# controller12.net
KiCad netlist of a schematic drawn in EAGLE
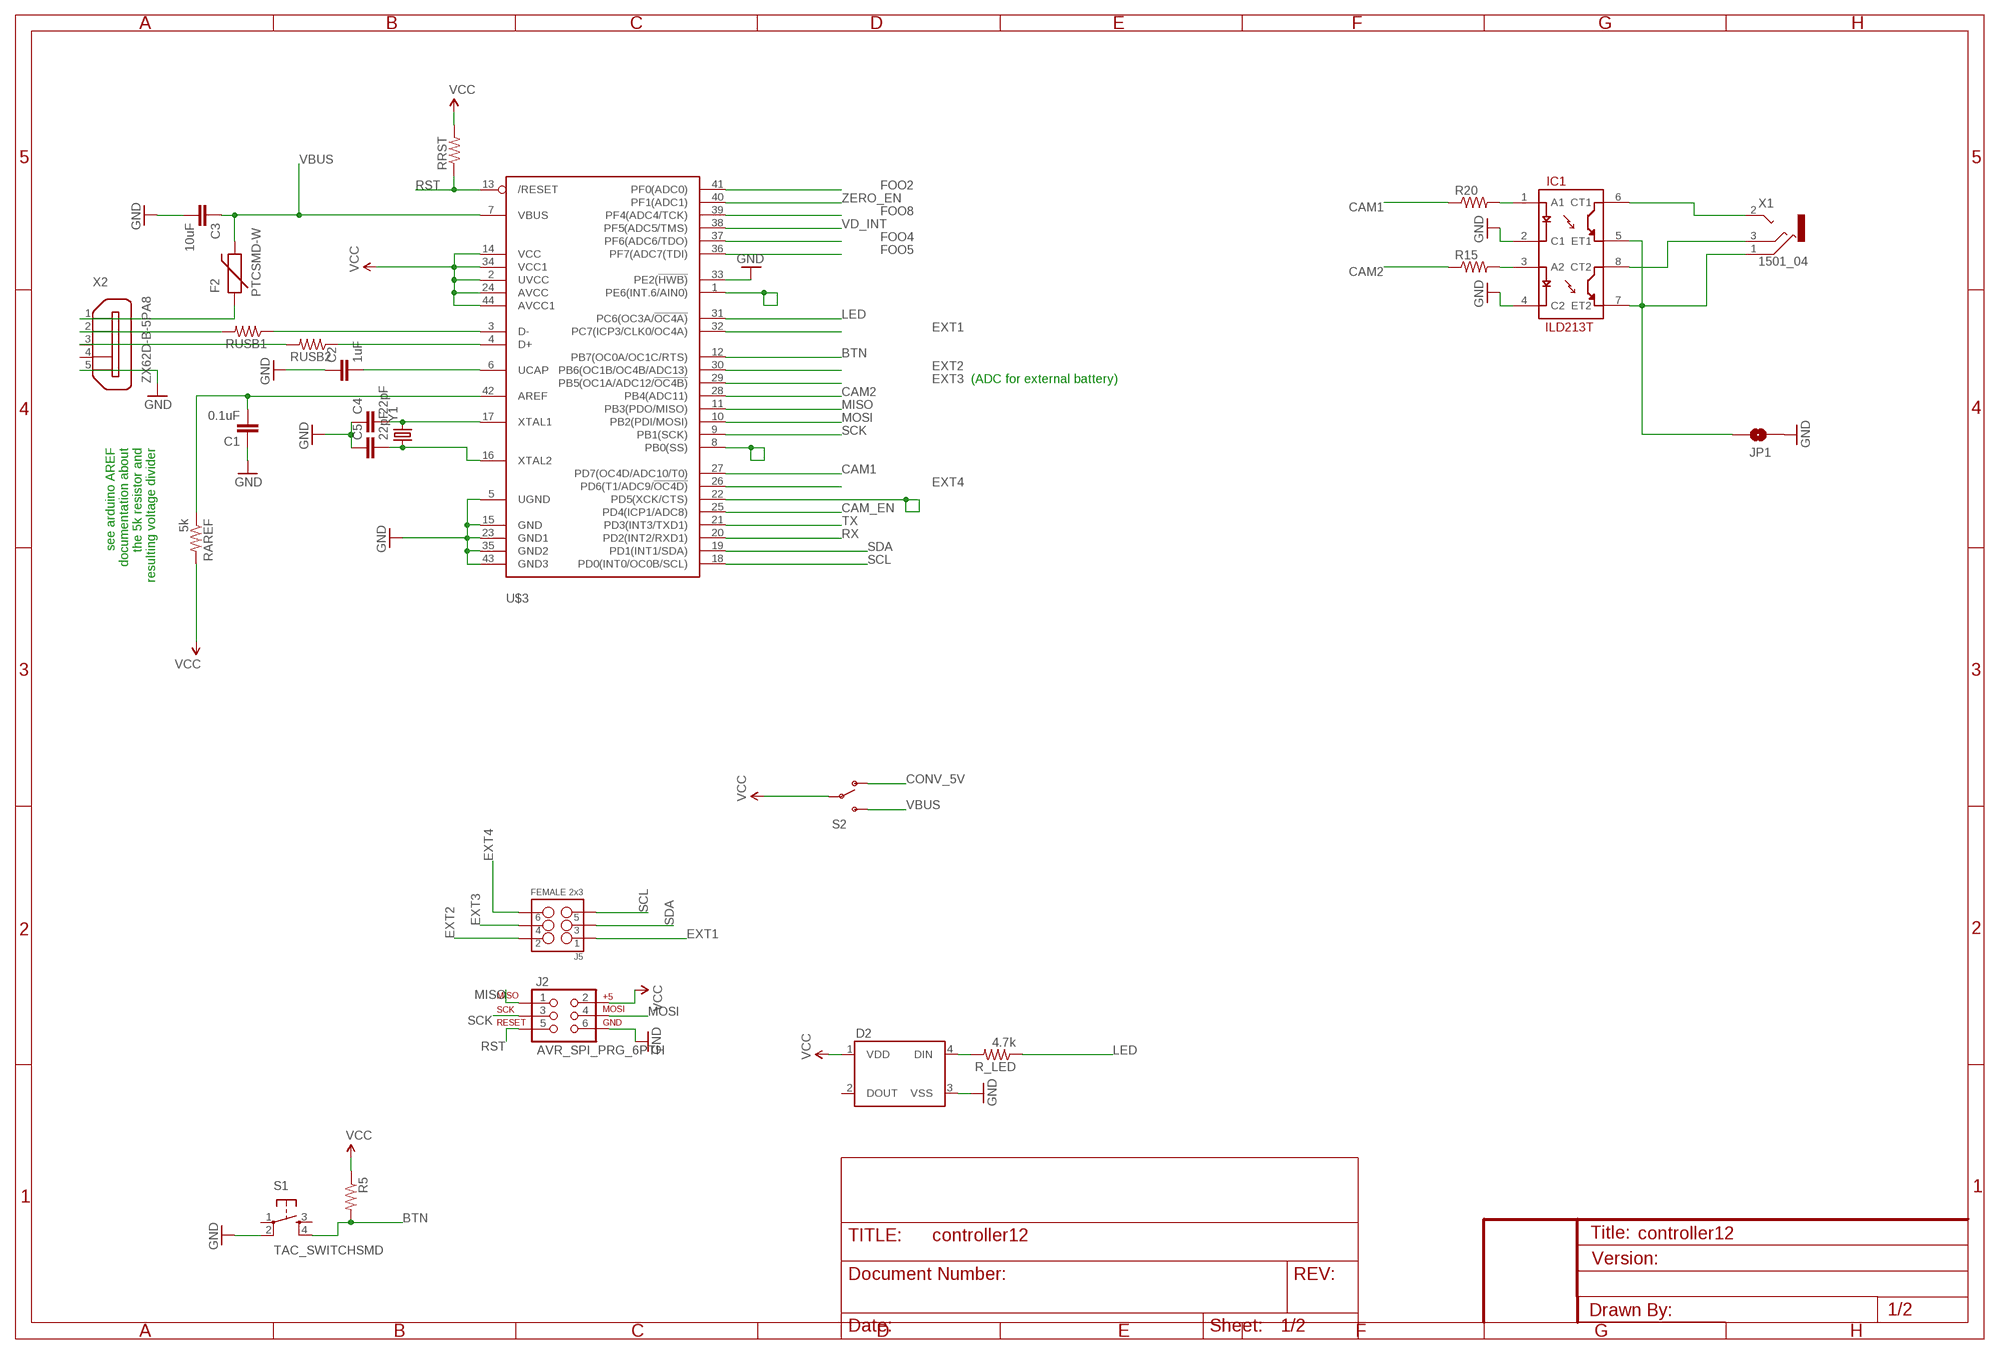
[diagram p0: schematic, sheet 1]
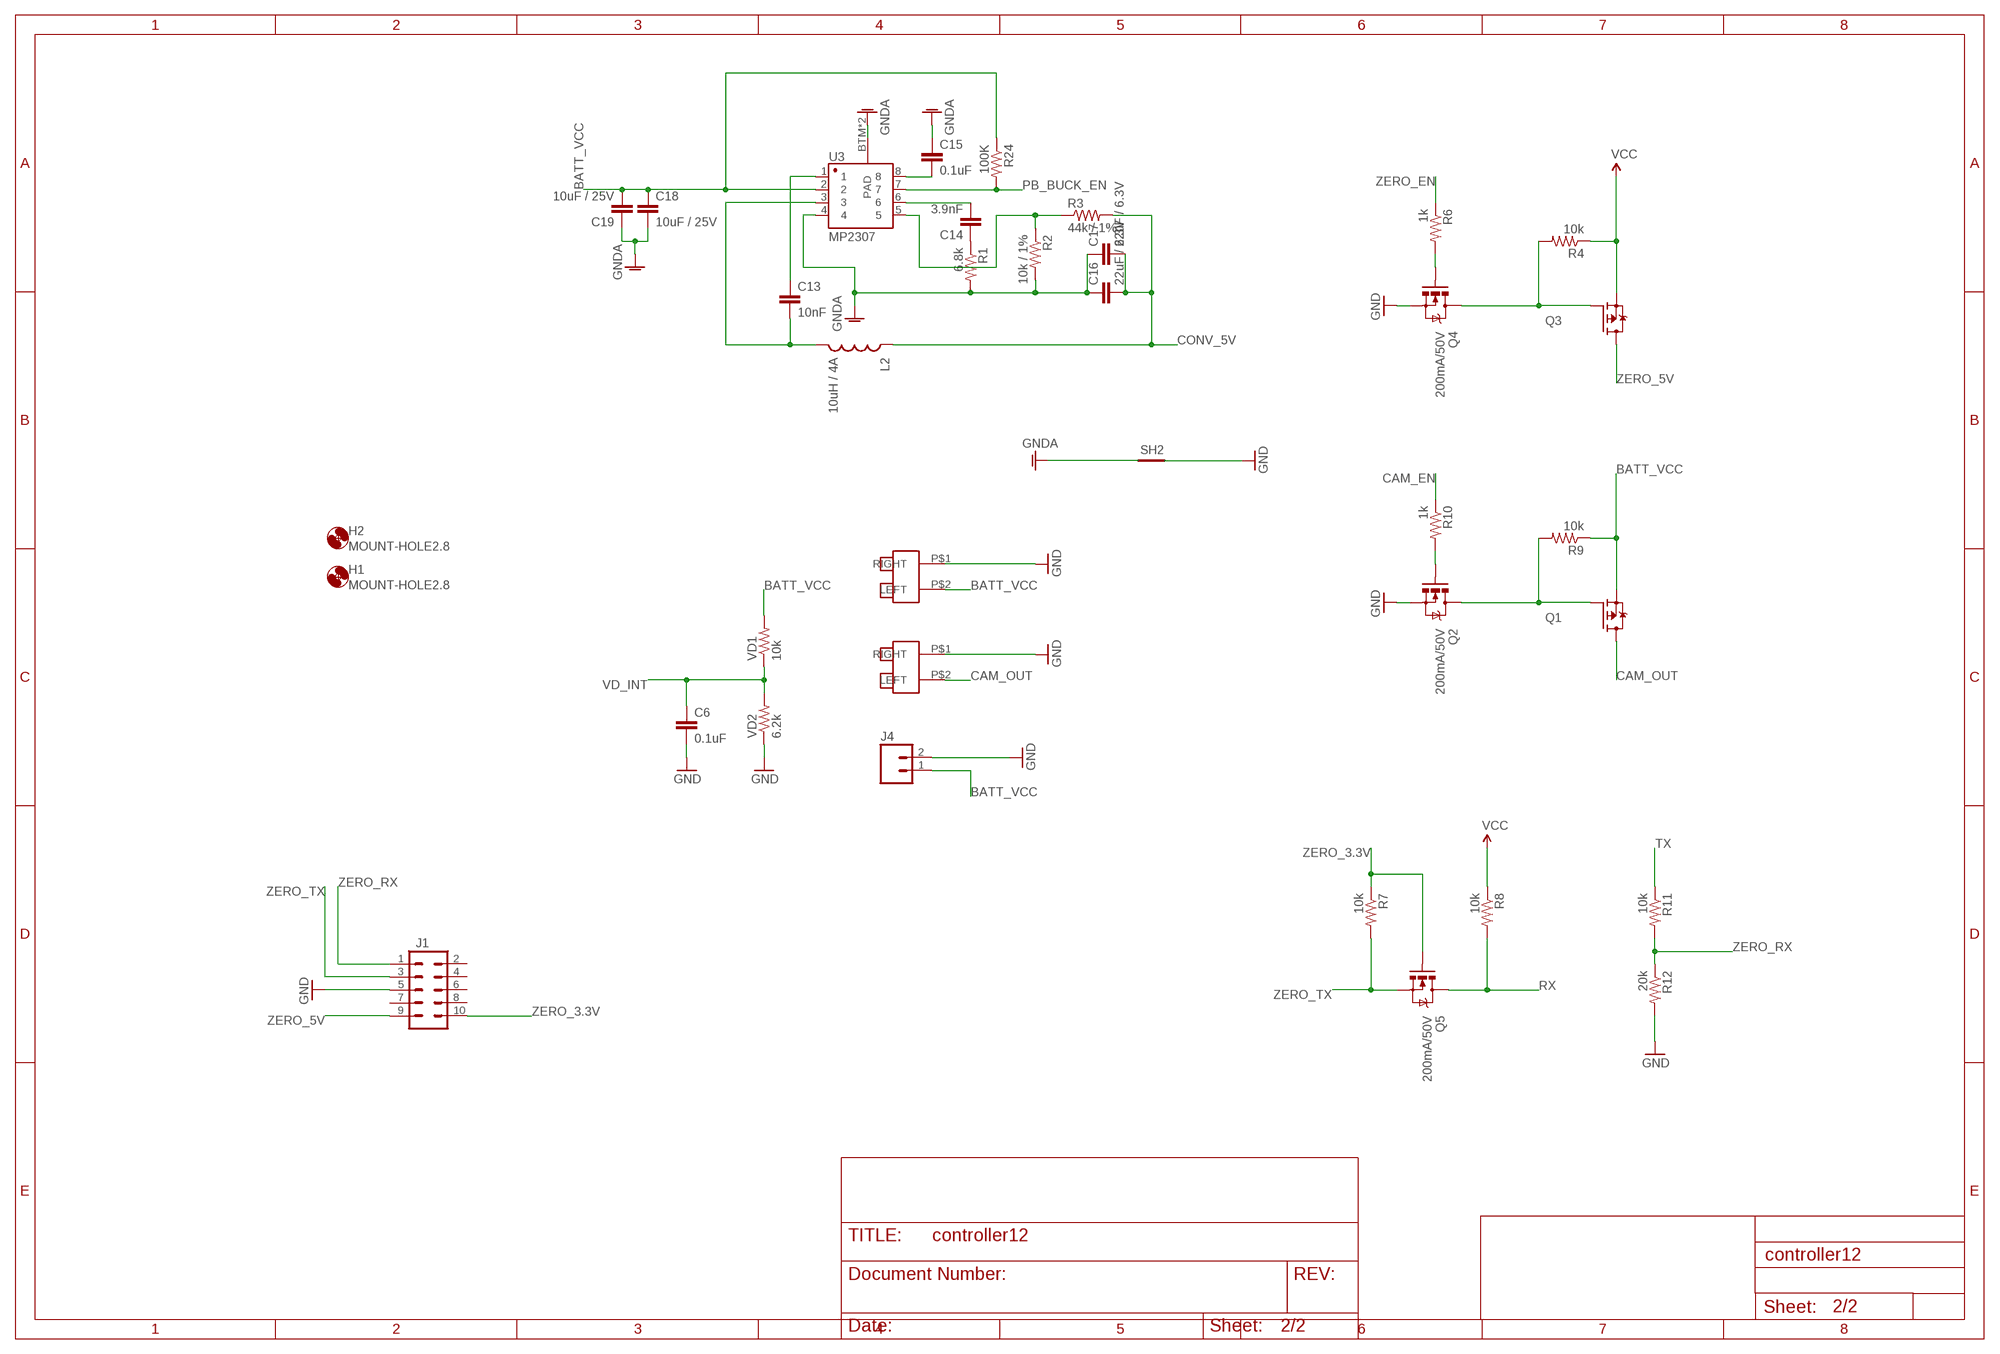
[diagram p1: schematic, sheet 2]

(export (version "E")
  (design (tool "Eeschema 10.0.6"))
  (components
    (comp (ref "C6")
      (value "0.1uF")
      (footprint "eagle-import:1206")
      (libsource (lib "eagle-import") (part "CAP1206"))
    )
    (comp (ref "C13")
      (value "10nF")
      (footprint "eagle-import:1206")
      (libsource (lib "eagle-import") (part "CAP1206"))
    )
    (comp (ref "C14")
      (value "3.9nF")
      (footprint "eagle-import:1206")
      (libsource (lib "eagle-import") (part "CAP1206"))
    )
    (comp (ref "C15")
      (value "0.1uF")
      (footprint "eagle-import:1206")
      (libsource (lib "eagle-import") (part "CAP1206"))
    )
    (comp (ref "C16")
      (value "22uF / 6.3V")
      (footprint "eagle-import:1210")
      (libsource (lib "eagle-import") (part "CAP1210"))
    )
    (comp (ref "C17")
      (value "22uF / 6.3V")
      (footprint "eagle-import:1210")
      (libsource (lib "eagle-import") (part "CAP1210"))
    )
    (comp (ref "C18")
      (value "10uF / 25V")
      (footprint "eagle-import:1210")
      (libsource (lib "eagle-import") (part "CAP1210"))
    )
    (comp (ref "C19")
      (value "10uF / 25V")
      (footprint "eagle-import:1210")
      (libsource (lib "eagle-import") (part "CAP1210"))
    )
    (comp (ref "H1")
      (value "MOUNT-HOLE2.8")
      (footprint "eagle-import:2,8")
      (libsource (lib "eagle-import") (part "MOUNT-HOLE2.8"))
    )
    (comp (ref "H2")
      (value "MOUNT-HOLE2.8")
      (footprint "eagle-import:2,8")
      (libsource (lib "eagle-import") (part "MOUNT-HOLE2.8"))
    )
    (comp (ref "J1")
      (value "M05X2PTH")
      (footprint "eagle-import:AVR_ICSP")
      (libsource (lib "eagle-import") (part "M05X2PTH"))
    )
    (comp (ref "J4")
      (value "M02PTH")
      (footprint "eagle-import:1X02")
      (libsource (lib "eagle-import") (part "M02PTH"))
    )
    (comp (ref "L2")
      (value "10uH / 4A")
      (footprint "eagle-import:SRU1038")
      (libsource (lib "eagle-import") (part "INDUCTORSRU1038"))
    )
    (comp (ref "Q1")
      (value "FDD4141TO252")
      (footprint "eagle-import:TO252")
      (libsource (lib "eagle-import") (part "FDD4141TO252"))
    )
    (comp (ref "Q2")
      (value "200mA/50V")
      (footprint "eagle-import:SOT23-3")
      (libsource (lib "eagle-import") (part "MOSFET-NCHANNELBSS138"))
    )
    (comp (ref "Q3")
      (value "FDD4141TO252")
      (footprint "eagle-import:TO252")
      (libsource (lib "eagle-import") (part "FDD4141TO252"))
    )
    (comp (ref "Q4")
      (value "200mA/50V")
      (footprint "eagle-import:SOT23-3")
      (libsource (lib "eagle-import") (part "MOSFET-NCHANNELBSS138"))
    )
    (comp (ref "Q5")
      (value "200mA/50V")
      (footprint "eagle-import:SOT23-3")
      (libsource (lib "eagle-import") (part "MOSFET-NCHANNELBSS138"))
    )
    (comp (ref "R1")
      (value "6.8k")
      (footprint "eagle-import:1206")
      (libsource (lib "eagle-import") (part "SparkFun-Resistors_RESISTOR1206"))
    )
    (comp (ref "R2")
      (value "10k / 1%")
      (footprint "eagle-import:1206")
      (libsource (lib "eagle-import") (part "SparkFun-Resistors_RESISTOR1206"))
    )
    (comp (ref "R3")
      (value "44k / 1%")
      (footprint "eagle-import:1206")
      (libsource (lib "eagle-import") (part "SparkFun-Resistors_RESISTOR1206"))
    )
    (comp (ref "R4")
      (value "10k")
      (footprint "eagle-import:1206")
      (libsource (lib "eagle-import") (part "SparkFun-Resistors_RESISTOR1206"))
    )
    (comp (ref "R6")
      (value "1k")
      (footprint "eagle-import:1206")
      (libsource (lib "eagle-import") (part "SparkFun-Resistors_RESISTOR1206"))
    )
    (comp (ref "R7")
      (value "10k")
      (footprint "eagle-import:1206")
      (libsource (lib "eagle-import") (part "SparkFun-Resistors_RESISTOR1206"))
    )
    (comp (ref "R8")
      (value "10k")
      (footprint "eagle-import:1206")
      (libsource (lib "eagle-import") (part "SparkFun-Resistors_RESISTOR1206"))
    )
    (comp (ref "R9")
      (value "10k")
      (footprint "eagle-import:1206")
      (libsource (lib "eagle-import") (part "SparkFun-Resistors_RESISTOR1206"))
    )
    (comp (ref "R10")
      (value "1k")
      (footprint "eagle-import:1206")
      (libsource (lib "eagle-import") (part "SparkFun-Resistors_RESISTOR1206"))
    )
    (comp (ref "R11")
      (value "10k")
      (footprint "eagle-import:1206")
      (libsource (lib "eagle-import") (part "SparkFun-Resistors_RESISTOR1206"))
    )
    (comp (ref "R12")
      (value "20k")
      (footprint "eagle-import:1206")
      (libsource (lib "eagle-import") (part "SparkFun-Resistors_RESISTOR1206"))
    )
    (comp (ref "R24")
      (value "100K")
      (footprint "eagle-import:1206")
      (libsource (lib "eagle-import") (part "SparkFun-Resistors_RESISTOR1206"))
    )
    (comp (ref "SH2")
      (value "SHORT-HT5")
      (footprint "eagle-import:SHORT_TOP-50")
      (libsource (lib "eagle-import") (part "SHORT-HT5"))
    )
    (comp (ref "U$4")
      (value "NANOFIT2")
      (footprint "eagle-import:NANOFIT2")
      (libsource (lib "eagle-import") (part "NANOFIT2"))
    )
    (comp (ref "U$5")
      (value "NANOFIT2")
      (footprint "eagle-import:NANOFIT2")
      (libsource (lib "eagle-import") (part "NANOFIT2"))
    )
    (comp (ref "U3")
      (value "MP2307")
      (footprint "eagle-import:SO08")
      (libsource (lib "eagle-import") (part "GENERIC-SOIC8MSGEQ7N-FILTER"))
    )
    (comp (ref "VD1")
      (value "10k")
      (footprint "eagle-import:1206")
      (libsource (lib "eagle-import") (part "RESISTOR1206"))
    )
    (comp (ref "VD2")
      (value "6.2k")
      (footprint "eagle-import:1206")
      (libsource (lib "eagle-import") (part "RESISTOR1206"))
    )
    (comp (ref "C1")
      (value "0.1uF")
      (footprint "eagle-import:1206")
      (libsource (lib "eagle-import") (part "CAP1206"))
    )
    (comp (ref "C2")
      (value "1uF")
      (footprint "eagle-import:1206")
      (libsource (lib "eagle-import") (part "CAP1206"))
    )
    (comp (ref "C3")
      (value "10uF")
      (footprint "eagle-import:1206")
      (libsource (lib "eagle-import") (part "SparkFun-Passives_CAP1206"))
    )
    (comp (ref "C4")
      (value "22pF")
      (footprint "eagle-import:1206")
      (libsource (lib "eagle-import") (part "SparkFun-Passives_CAP1206"))
    )
    (comp (ref "C5")
      (value "22pF")
      (footprint "eagle-import:1206")
      (libsource (lib "eagle-import") (part "SparkFun-Passives_CAP1206"))
    )
    (comp (ref "D2")
      (value "WS2812B")
      (footprint "eagle-import:WS2812B")
      (libsource (lib "eagle-import") (part "WS2812B"))
    )
    (comp (ref "F2")
      (value "PTCSMD-W")
      (footprint "eagle-import:PTC-1206-WIDE")
      (libsource (lib "eagle-import") (part "PTCSMD-W"))
    )
    (comp (ref "IC1")
      (value "ILD213T")
      (footprint "eagle-import:SO08")
      (libsource (lib "eagle-import") (part "ILD213T"))
    )
    (comp (ref "J2")
      (value "AVR_SPI_PRG_6PTH")
      (footprint "eagle-import:2X3")
      (libsource (lib "eagle-import") (part "AVR_SPI_PRG_6PTH"))
    )
    (comp (ref "J5")
      (value "FEMALE 2x3")
      (footprint "eagle-import:2X3")
      (libsource (lib "eagle-import") (part "M03X2FEMALE"))
    )
    (comp (ref "JP1")
      (value "JUMPER-PAD-2-NOYES_SILK")
      (footprint "eagle-import:PAD-JUMPER-2-NO_YES_SILK")
      (libsource (lib "eagle-import") (part "JUMPER-PAD-2-NOYES_SILK"))
    )
    (comp (ref "R5")
      (value "RESISTOR1206")
      (footprint "eagle-import:1206")
      (libsource (lib "eagle-import") (part "RESISTOR1206"))
    )
    (comp (ref "R15")
      (value "RESISTOR1206")
      (footprint "eagle-import:1206")
      (libsource (lib "eagle-import") (part "RESISTOR1206"))
    )
    (comp (ref "R20")
      (value "RESISTOR1206")
      (footprint "eagle-import:1206")
      (libsource (lib "eagle-import") (part "RESISTOR1206"))
    )
    (comp (ref "RAREF")
      (value "5k")
      (footprint "eagle-import:1206")
      (libsource (lib "eagle-import") (part "RESISTOR1206"))
    )
    (comp (ref "RRST")
      (value "RESISTOR1206")
      (footprint "eagle-import:1206")
      (libsource (lib "eagle-import") (part "RESISTOR1206"))
    )
    (comp (ref "RUSB1")
      (value "RESISTOR1206")
      (footprint "eagle-import:1206")
      (libsource (lib "eagle-import") (part "RESISTOR1206"))
    )
    (comp (ref "RUSB2")
      (value "RESISTOR1206")
      (footprint "eagle-import:1206")
      (libsource (lib "eagle-import") (part "RESISTOR1206"))
    )
    (comp (ref "R_LED")
      (value "4.7k")
      (footprint "eagle-import:1206")
      (libsource (lib "eagle-import") (part "SparkFun-Resistors_RESISTOR1206"))
    )
    (comp (ref "S1")
      (value "TAC_SWITCHSMD")
      (footprint "eagle-import:TACTILE-PTH")
      (libsource (lib "eagle-import") (part "TAC_SWITCHPTH"))
    )
    (comp (ref "S2")
      (value "SWITCH-SPDTSMD2")
      (footprint "eagle-import:SWITCH-SPDT-SMD")
      (libsource (lib "eagle-import") (part "SWITCH-SPDTSMD2"))
    )
    (comp (ref "U$3")
      (value "ATMEGA32U4-AU")
      (footprint "eagle-import:TQFP44")
      (libsource (lib "eagle-import") (part "ATMEGA32U4-AU"))
    )
    (comp (ref "X1")
      (value "1501_04")
      (footprint "eagle-import:1501_05")
      (libsource (lib "eagle-import") (part "1501_04"))
    )
    (comp (ref "X2")
      (value "ZX62D-B-5PA8")
      (footprint "eagle-import:ZX62D-B-5PA8")
      (fields (field (name "MF") "Hirose"))
      (libsource (lib "eagle-import") (part "ZX62D-B-5PA8"))
    )
    (comp (ref "Y1")
      (value "CRYSTALCRYSTAL-SMD-5X3-16MHZ")
      (footprint "eagle-import:CRYSTAL-SMD-5X3")
      (libsource (lib "eagle-import") (part "CRYSTALCRYSTAL-SMD-5X3-16MHZ"))
    )
  )
  (nets
    (net (code "1") (name "BATT_VCC") (class "Default")
      (node (ref "C18") (pin "1") (pinfunction "1_1") (pintype "passive"))
      (node (ref "C19") (pin "2") (pinfunction "2_2") (pintype "passive"))
      (node (ref "J4") (pin "1") (pinfunction "1_1") (pintype "passive"))
      (node (ref "Q1") (pin "2") (pinfunction "S_2") (pintype "passive"))
      (node (ref "R24") (pin "1") (pinfunction "1_1") (pintype "passive"))
      (node (ref "R9") (pin "1") (pinfunction "1_1") (pintype "passive"))
      (node (ref "U$4") (pin "P$2") (pinfunction "LEFT_P$2") (pintype "bidirectional"))
      (node (ref "U3") (pin "2") (pinfunction "2_2") (pintype "bidirectional"))
      (node (ref "VD1") (pin "2") (pinfunction "2_2") (pintype "passive"))
    )
    (net (code "2") (name "BTN") (class "Default")
      (node (ref "R5") (pin "2") (pinfunction "2_2") (pintype "passive"))
      (node (ref "S1") (pin "4") (pinfunction "4_4") (pintype "passive"))
      (node (ref "U$3") (pin "12") (pinfunction "PB7(OC0A/OC1C/RTS)_12") (pintype "bidirectional"))
    )
    (net (code "3") (name "CAM1") (class "Default")
      (node (ref "R20") (pin "1") (pinfunction "1_1") (pintype "passive"))
      (node (ref "U$3") (pin "27") (pinfunction "PD7(OC4D/ADC10/T0)_27") (pintype "bidirectional"))
    )
    (net (code "4") (name "CAM2") (class "Default")
      (node (ref "R15") (pin "1") (pinfunction "1_1") (pintype "passive"))
      (node (ref "U$3") (pin "28") (pinfunction "PB4(ADC11)_28") (pintype "bidirectional"))
    )
    (net (code "5") (name "CAM_EN") (class "Default")
      (node (ref "R10") (pin "1") (pinfunction "1_1") (pintype "passive"))
      (node (ref "U$3") (pin "25") (pinfunction "PD4(ICP1/ADC8)_25") (pintype "bidirectional"))
    )
    (net (code "6") (name "CAM_OUT") (class "Default")
      (node (ref "Q1") (pin "3") (pinfunction "D_3") (pintype "passive"))
      (node (ref "U$5") (pin "P$2") (pinfunction "LEFT_P$2") (pintype "bidirectional"))
    )
    (net (code "7") (name "CONV_5V") (class "Default")
      (node (ref "C16") (pin "2") (pinfunction "2_2") (pintype "passive"))
      (node (ref "C17") (pin "2") (pinfunction "2_2") (pintype "passive"))
      (node (ref "L2") (pin "1") (pinfunction "1_1") (pintype "passive"))
      (node (ref "R3") (pin "2") (pinfunction "2_2") (pintype "passive"))
      (node (ref "S2") (pin "1") (pinfunction "O_1") (pintype "passive"))
    )
    (net (code "8") (name "EXT1") (class "Default")
      (node (ref "J5") (pin "1") (pinfunction "1_1") (pintype "bidirectional"))
      (node (ref "U$3") (pin "32") (pinfunction "PC7(ICP3/CLK0/OC4A)_32") (pintype "bidirectional"))
    )
    (net (code "9") (name "EXT2") (class "Default")
      (node (ref "J5") (pin "2") (pinfunction "2_2") (pintype "bidirectional"))
      (node (ref "U$3") (pin "30") (pinfunction "PB6(OC1B/OC4B/ADC13)_30") (pintype "bidirectional"))
    )
    (net (code "10") (name "EXT3") (class "Default")
      (node (ref "J5") (pin "4") (pinfunction "4_4") (pintype "bidirectional"))
      (node (ref "U$3") (pin "29") (pinfunction "PB5(OC1A/ADC12/~{OC4B})_29") (pintype "bidirectional"))
    )
    (net (code "11") (name "EXT4") (class "Default")
      (node (ref "J5") (pin "6") (pinfunction "6_6") (pintype "bidirectional"))
      (node (ref "U$3") (pin "26") (pinfunction "PD6(T1/ADC9/~{OC4D})_26") (pintype "bidirectional"))
    )
    (net (code "12") (name "FOO2") (class "Default")
      (node (ref "U$3") (pin "41") (pinfunction "PF0(ADC0)_41") (pintype "bidirectional"))
    )
    (net (code "13") (name "FOO4") (class "Default")
      (node (ref "U$3") (pin "37") (pinfunction "PF6(ADC6/TDO)_37") (pintype "bidirectional"))
    )
    (net (code "14") (name "FOO5") (class "Default")
      (node (ref "U$3") (pin "36") (pinfunction "PF7(ADC7(TDI)_36") (pintype "bidirectional"))
    )
    (net (code "15") (name "FOO8") (class "Default")
      (node (ref "U$3") (pin "39") (pinfunction "PF4(ADC4/TCK)_39") (pintype "bidirectional"))
    )
    (net (code "16") (name "GND") (class "Default")
      (node (ref "C1") (pin "1") (pinfunction "1_1") (pintype "passive"))
      (node (ref "C2") (pin "1") (pinfunction "1_1") (pintype "passive"))
      (node (ref "C3") (pin "2") (pinfunction "2_2") (pintype "passive"))
      (node (ref "C4") (pin "1") (pinfunction "1_1") (pintype "passive"))
      (node (ref "C5") (pin "1") (pinfunction "1_1") (pintype "passive"))
      (node (ref "C6") (pin "2") (pinfunction "2_2") (pintype "passive"))
      (node (ref "D2") (pin "3") (pinfunction "VSS_3") (pintype "power_in"))
      (node (ref "IC1") (pin "2") (pinfunction "C1_2") (pintype "bidirectional"))
      (node (ref "IC1") (pin "4") (pinfunction "C2_4") (pintype "bidirectional"))
      (node (ref "J1") (pin "5") (pinfunction "5_5") (pintype "passive"))
      (node (ref "J2") (pin "6") (pinfunction "6_6") (pintype "passive"))
      (node (ref "J4") (pin "2") (pinfunction "2_2") (pintype "passive"))
      (node (ref "JP1") (pin "1") (pinfunction "1_1") (pintype "passive"))
      (node (ref "Q2") (pin "2") (pinfunction "S_2") (pintype "passive"))
      (node (ref "Q4") (pin "2") (pinfunction "S_2") (pintype "passive"))
      (node (ref "R12") (pin "2") (pinfunction "2_2") (pintype "passive"))
      (node (ref "S1") (pin "2") (pinfunction "2_2") (pintype "passive"))
      (node (ref "SH2") (pin "2") (pinfunction "P$2_2") (pintype "bidirectional"))
      (node (ref "U$3") (pin "15") (pinfunction "GND_15") (pintype "bidirectional"))
      (node (ref "U$3") (pin "23") (pinfunction "GND1_23") (pintype "bidirectional"))
      (node (ref "U$3") (pin "33") (pinfunction "PE2(~{HWB})_33") (pintype "bidirectional"))
      (node (ref "U$3") (pin "35") (pinfunction "GND2_35") (pintype "bidirectional"))
      (node (ref "U$3") (pin "43") (pinfunction "GND3_43") (pintype "bidirectional"))
      (node (ref "U$3") (pin "5") (pinfunction "UGND_5") (pintype "bidirectional"))
      (node (ref "U$4") (pin "P$1") (pinfunction "RIGHT_P$1") (pintype "bidirectional"))
      (node (ref "U$5") (pin "P$1") (pinfunction "RIGHT_P$1") (pintype "bidirectional"))
      (node (ref "VD2") (pin "1") (pinfunction "1_1") (pintype "passive"))
      (node (ref "X2") (pin "5") (pinfunction "5_5") (pintype "passive"))
    )
    (net (code "17") (name "GNDA") (class "Default")
      (node (ref "C15") (pin "1") (pinfunction "1_1") (pintype "passive"))
      (node (ref "C16") (pin "1") (pinfunction "1_1") (pintype "passive"))
      (node (ref "C17") (pin "1") (pinfunction "1_1") (pintype "passive"))
      (node (ref "C18") (pin "2") (pinfunction "2_2") (pintype "passive"))
      (node (ref "C19") (pin "1") (pinfunction "1_1") (pintype "passive"))
      (node (ref "R1") (pin "2") (pinfunction "2_2") (pintype "passive"))
      (node (ref "R2") (pin "2") (pinfunction "2_2") (pintype "passive"))
      (node (ref "SH2") (pin "1") (pinfunction "P$1_1") (pintype "bidirectional"))
      (node (ref "U3") (pin "4") (pinfunction "4_4") (pintype "bidirectional"))
      (node (ref "U3") (pin "BTM") (pinfunction "PAD_BTM") (pintype "bidirectional"))
      (node (ref "U3") (pin "P$1") (pinfunction "PAD_P$1") (pintype "bidirectional"))
    )
    (net (code "18") (name "LED") (class "Default")
      (node (ref "R_LED") (pin "1") (pinfunction "1_1") (pintype "passive"))
      (node (ref "U$3") (pin "31") (pinfunction "PC6(OC3A/~{OC4A})_31") (pintype "bidirectional"))
    )
    (net (code "19") (name "MISO") (class "Default")
      (node (ref "J2") (pin "1") (pinfunction "1_1") (pintype "passive"))
      (node (ref "U$3") (pin "11") (pinfunction "PB3(PDO/MISO)_11") (pintype "bidirectional"))
    )
    (net (code "20") (name "MOSI") (class "Default")
      (node (ref "J2") (pin "4") (pinfunction "4_4") (pintype "passive"))
      (node (ref "U$3") (pin "10") (pinfunction "PB2(PDI/MOSI)_10") (pintype "bidirectional"))
    )
    (net (code "21") (name "Net-(C13-Pad1)") (class "Default")
      (node (ref "C13") (pin "1") (pinfunction "1_1") (pintype "passive"))
      (node (ref "U3") (pin "1") (pinfunction "1_1") (pintype "bidirectional"))
    )
    (net (code "22") (name "Net-(C13-Pad2)") (class "Default")
      (node (ref "C13") (pin "2") (pinfunction "2_2") (pintype "passive"))
      (node (ref "L2") (pin "2") (pinfunction "2_2") (pintype "passive"))
      (node (ref "U3") (pin "3") (pinfunction "3_3") (pintype "bidirectional"))
    )
    (net (code "23") (name "Net-(C14-Pad1)") (class "Default")
      (node (ref "C14") (pin "1") (pinfunction "1_1") (pintype "passive"))
      (node (ref "R1") (pin "1") (pinfunction "1_1") (pintype "passive"))
    )
    (net (code "24") (name "Net-(C14-Pad2)") (class "Default")
      (node (ref "C14") (pin "2") (pinfunction "2_2") (pintype "passive"))
      (node (ref "U3") (pin "6") (pinfunction "6_6") (pintype "bidirectional"))
    )
    (net (code "25") (name "Net-(C15-Pad2)") (class "Default")
      (node (ref "C15") (pin "2") (pinfunction "2_2") (pintype "passive"))
      (node (ref "U3") (pin "8") (pinfunction "8_8") (pintype "bidirectional"))
    )
    (net (code "26") (name "Net-(D2-DIN)") (class "Default")
      (node (ref "D2") (pin "4") (pinfunction "DIN_4") (pintype "input"))
      (node (ref "R_LED") (pin "2") (pinfunction "2_2") (pintype "passive"))
    )
    (net (code "27") (name "Net-(F2-Pad1)") (class "Default")
      (node (ref "F2") (pin "1") (pinfunction "1_1") (pintype "bidirectional"))
      (node (ref "X2") (pin "1") (pinfunction "1_1") (pintype "passive"))
    )
    (net (code "28") (name "Net-(IC1-A1)") (class "Default")
      (node (ref "IC1") (pin "1") (pinfunction "A1_1") (pintype "bidirectional"))
      (node (ref "R20") (pin "2") (pinfunction "2_2") (pintype "passive"))
    )
    (net (code "29") (name "Net-(IC1-A2)") (class "Default")
      (node (ref "IC1") (pin "3") (pinfunction "A2_3") (pintype "bidirectional"))
      (node (ref "R15") (pin "2") (pinfunction "2_2") (pintype "passive"))
    )
    (net (code "30") (name "Net-(IC1-CT1)") (class "Default")
      (node (ref "IC1") (pin "6") (pinfunction "CT1_6") (pintype "bidirectional"))
      (node (ref "X1") (pin "2") (pinfunction "2_2") (pintype "passive"))
    )
    (net (code "31") (name "Net-(IC1-CT2)") (class "Default")
      (node (ref "IC1") (pin "8") (pinfunction "CT2_8") (pintype "bidirectional"))
      (node (ref "X1") (pin "3") (pinfunction "3_3") (pintype "passive"))
    )
    (net (code "32") (name "Net-(IC1-ET1)") (class "Default")
      (node (ref "IC1") (pin "5") (pinfunction "ET1_5") (pintype "bidirectional"))
      (node (ref "IC1") (pin "7") (pinfunction "ET2_7") (pintype "bidirectional"))
      (node (ref "JP1") (pin "2") (pinfunction "2_2") (pintype "passive"))
      (node (ref "X1") (pin "1") (pinfunction "1_1") (pintype "passive"))
    )
    (net (code "33") (name "Net-(Q1-G)") (class "Default")
      (node (ref "Q1") (pin "1") (pinfunction "G_1") (pintype "passive"))
      (node (ref "Q2") (pin "3") (pinfunction "D_3") (pintype "passive"))
      (node (ref "R9") (pin "2") (pinfunction "2_2") (pintype "passive"))
    )
    (net (code "34") (name "Net-(Q2-G)") (class "Default")
      (node (ref "Q2") (pin "1") (pinfunction "G_1") (pintype "passive"))
      (node (ref "R10") (pin "2") (pinfunction "2_2") (pintype "passive"))
    )
    (net (code "35") (name "Net-(Q3-G)") (class "Default")
      (node (ref "Q3") (pin "1") (pinfunction "G_1") (pintype "passive"))
      (node (ref "Q4") (pin "3") (pinfunction "D_3") (pintype "passive"))
      (node (ref "R4") (pin "2") (pinfunction "2_2") (pintype "passive"))
    )
    (net (code "36") (name "Net-(Q4-G)") (class "Default")
      (node (ref "Q4") (pin "1") (pinfunction "G_1") (pintype "passive"))
      (node (ref "R6") (pin "2") (pinfunction "2_2") (pintype "passive"))
    )
    (net (code "37") (name "Net-(R2-Pad1)") (class "Default")
      (node (ref "R2") (pin "1") (pinfunction "1_1") (pintype "passive"))
      (node (ref "R3") (pin "1") (pinfunction "1_1") (pintype "passive"))
      (node (ref "U3") (pin "5") (pinfunction "5_5") (pintype "bidirectional"))
    )
    (net (code "38") (name "Net-(RUSB1-Pad2)") (class "Default")
      (node (ref "RUSB1") (pin "2") (pinfunction "2_2") (pintype "passive"))
      (node (ref "X2") (pin "2") (pinfunction "2_2") (pintype "passive"))
    )
    (net (code "39") (name "Net-(RUSB2-Pad2)") (class "Default")
      (node (ref "RUSB2") (pin "2") (pinfunction "2_2") (pintype "passive"))
      (node (ref "X2") (pin "3") (pinfunction "3_3") (pintype "passive"))
    )
    (net (code "40") (name "Net-(U$3-AREF)") (class "Default")
      (node (ref "C1") (pin "2") (pinfunction "2_2") (pintype "passive"))
      (node (ref "RAREF") (pin "1") (pinfunction "1_1") (pintype "passive"))
      (node (ref "U$3") (pin "42") (pinfunction "AREF_42") (pintype "bidirectional"))
    )
    (net (code "41") (name "Net-(U$3-D+)") (class "Default")
      (node (ref "RUSB2") (pin "1") (pinfunction "1_1") (pintype "passive"))
      (node (ref "U$3") (pin "4") (pinfunction "D+_4") (pintype "bidirectional"))
    )
    (net (code "42") (name "Net-(U$3-D-)") (class "Default")
      (node (ref "RUSB1") (pin "1") (pinfunction "1_1") (pintype "passive"))
      (node (ref "U$3") (pin "3") (pinfunction "D-_3") (pintype "bidirectional"))
    )
    (net (code "43") (name "Net-(U$3-UCAP)") (class "Default")
      (node (ref "C2") (pin "2") (pinfunction "2_2") (pintype "passive"))
      (node (ref "U$3") (pin "6") (pinfunction "UCAP_6") (pintype "bidirectional"))
    )
    (net (code "44") (name "Net-(U$3-XTAL1)") (class "Default")
      (node (ref "C4") (pin "2") (pinfunction "2_2") (pintype "passive"))
      (node (ref "U$3") (pin "17") (pinfunction "XTAL1_17") (pintype "bidirectional"))
      (node (ref "Y1") (pin "3") (pinfunction "2_3") (pintype "passive"))
    )
    (net (code "45") (name "Net-(U$3-XTAL2)") (class "Default")
      (node (ref "C5") (pin "2") (pinfunction "2_2") (pintype "passive"))
      (node (ref "U$3") (pin "16") (pinfunction "XTAL2_16") (pintype "bidirectional"))
      (node (ref "Y1") (pin "1") (pinfunction "1_1") (pintype "passive"))
    )
    (net (code "46") (name "PB_BUCK_EN") (class "Default")
      (node (ref "R24") (pin "2") (pinfunction "2_2") (pintype "passive"))
      (node (ref "U3") (pin "7") (pinfunction "7_7") (pintype "bidirectional"))
    )
    (net (code "47") (name "RST") (class "Default")
      (node (ref "J2") (pin "5") (pinfunction "5_5") (pintype "passive"))
      (node (ref "RRST") (pin "1") (pinfunction "1_1") (pintype "passive"))
      (node (ref "U$3") (pin "13") (pinfunction "/RESET_13") (pintype "bidirectional"))
    )
    (net (code "48") (name "RX") (class "Default")
      (node (ref "Q5") (pin "3") (pinfunction "D_3") (pintype "passive"))
      (node (ref "R8") (pin "2") (pinfunction "2_2") (pintype "passive"))
      (node (ref "U$3") (pin "20") (pinfunction "PD2(INT2/RXD1)_20") (pintype "bidirectional"))
    )
    (net (code "49") (name "SCK") (class "Default")
      (node (ref "J2") (pin "3") (pinfunction "3_3") (pintype "passive"))
      (node (ref "U$3") (pin "9") (pinfunction "PB1(SCK)_9") (pintype "bidirectional"))
    )
    (net (code "50") (name "SCL") (class "Default")
      (node (ref "J5") (pin "5") (pinfunction "5_5") (pintype "bidirectional"))
      (node (ref "U$3") (pin "18") (pinfunction "PD0(INT0/OC0B/SCL)_18") (pintype "bidirectional"))
    )
    (net (code "51") (name "SDA") (class "Default")
      (node (ref "J5") (pin "3") (pinfunction "3_3") (pintype "bidirectional"))
      (node (ref "U$3") (pin "19") (pinfunction "PD1(INT1/SDA)_19") (pintype "bidirectional"))
    )
    (net (code "52") (name "TX") (class "Default")
      (node (ref "R11") (pin "1") (pinfunction "1_1") (pintype "passive"))
      (node (ref "U$3") (pin "21") (pinfunction "PD3(INT3/TXD1)_21") (pintype "bidirectional"))
    )
    (net (code "53") (name "VBUS") (class "Default")
      (node (ref "C3") (pin "1") (pinfunction "1_1") (pintype "passive"))
      (node (ref "F2") (pin "2") (pinfunction "2_2") (pintype "bidirectional"))
      (node (ref "S2") (pin "3") (pinfunction "S_3") (pintype "passive"))
      (node (ref "U$3") (pin "7") (pinfunction "VBUS_7") (pintype "bidirectional"))
    )
    (net (code "54") (name "VCC") (class "Default")
      (node (ref "D2") (pin "1") (pinfunction "VDD_1") (pintype "power_in"))
      (node (ref "J2") (pin "2") (pinfunction "2_2") (pintype "passive"))
      (node (ref "Q3") (pin "2") (pinfunction "S_2") (pintype "passive"))
      (node (ref "R4") (pin "1") (pinfunction "1_1") (pintype "passive"))
      (node (ref "R5") (pin "1") (pinfunction "1_1") (pintype "passive"))
      (node (ref "R8") (pin "1") (pinfunction "1_1") (pintype "passive"))
      (node (ref "RAREF") (pin "2") (pinfunction "2_2") (pintype "passive"))
      (node (ref "RRST") (pin "2") (pinfunction "2_2") (pintype "passive"))
      (node (ref "S2") (pin "2") (pinfunction "P_2") (pintype "passive"))
      (node (ref "U$3") (pin "14") (pinfunction "VCC_14") (pintype "bidirectional"))
      (node (ref "U$3") (pin "2") (pinfunction "UVCC_2") (pintype "bidirectional"))
      (node (ref "U$3") (pin "24") (pinfunction "AVCC_24") (pintype "bidirectional"))
      (node (ref "U$3") (pin "34") (pinfunction "VCC1_34") (pintype "bidirectional"))
      (node (ref "U$3") (pin "44") (pinfunction "AVCC1_44") (pintype "bidirectional"))
    )
    (net (code "55") (name "VD_INT") (class "Default")
      (node (ref "C6") (pin "1") (pinfunction "1_1") (pintype "passive"))
      (node (ref "U$3") (pin "38") (pinfunction "PF5(ADC5/TMS)_38") (pintype "bidirectional"))
      (node (ref "VD1") (pin "1") (pinfunction "1_1") (pintype "passive"))
      (node (ref "VD2") (pin "2") (pinfunction "2_2") (pintype "passive"))
    )
    (net (code "56") (name "ZERO_3.3V") (class "Default")
      (node (ref "J1") (pin "10") (pinfunction "10_10") (pintype "passive"))
      (node (ref "Q5") (pin "1") (pinfunction "G_1") (pintype "passive"))
      (node (ref "R7") (pin "1") (pinfunction "1_1") (pintype "passive"))
    )
    (net (code "57") (name "ZERO_5V") (class "Default")
      (node (ref "J1") (pin "9") (pinfunction "9_9") (pintype "passive"))
      (node (ref "Q3") (pin "3") (pinfunction "D_3") (pintype "passive"))
    )
    (net (code "58") (name "ZERO_EN") (class "Default")
      (node (ref "R6") (pin "1") (pinfunction "1_1") (pintype "passive"))
      (node (ref "U$3") (pin "40") (pinfunction "PF1(ADC1)_40") (pintype "bidirectional"))
    )
    (net (code "59") (name "ZERO_RX") (class "Default")
      (node (ref "J1") (pin "1") (pinfunction "1_1") (pintype "passive"))
      (node (ref "R11") (pin "2") (pinfunction "2_2") (pintype "passive"))
      (node (ref "R12") (pin "1") (pinfunction "1_1") (pintype "passive"))
    )
    (net (code "60") (name "ZERO_TX") (class "Default")
      (node (ref "J1") (pin "3") (pinfunction "3_3") (pintype "passive"))
      (node (ref "Q5") (pin "2") (pinfunction "S_2") (pintype "passive"))
      (node (ref "R7") (pin "2") (pinfunction "2_2") (pintype "passive"))
    )
    (net (code "61") (name "unconnected-(D2-DOUT-Pad2)") (class "Default")
      (node (ref "D2") (pin "2") (pinfunction "DOUT_2") (pintype "output"))
    )
    (net (code "62") (name "unconnected-(J1-Pad2)") (class "Default")
      (node (ref "J1") (pin "2") (pinfunction "2_2") (pintype "passive"))
    )
    (net (code "63") (name "unconnected-(J1-Pad4)") (class "Default")
      (node (ref "J1") (pin "4") (pinfunction "4_4") (pintype "passive"))
    )
    (net (code "64") (name "unconnected-(J1-Pad6)") (class "Default")
      (node (ref "J1") (pin "6") (pinfunction "6_6") (pintype "passive"))
    )
    (net (code "65") (name "unconnected-(J1-Pad7)") (class "Default")
      (node (ref "J1") (pin "7") (pinfunction "7_7") (pintype "passive"))
    )
    (net (code "66") (name "unconnected-(J1-Pad8)") (class "Default")
      (node (ref "J1") (pin "8") (pinfunction "8_8") (pintype "passive"))
    )
    (net (code "67") (name "unconnected-(S1-Pad1)") (class "Default")
      (node (ref "S1") (pin "1") (pinfunction "1_1") (pintype "passive"))
    )
    (net (code "68") (name "unconnected-(S1-Pad3)") (class "Default")
      (node (ref "S1") (pin "3") (pinfunction "3_3") (pintype "passive"))
    )
    (net (code "69") (name "unconnected-(U$3-PB0(SS)-Pad8)") (class "Default")
      (node (ref "U$3") (pin "8") (pinfunction "PB0(SS)_8") (pintype "bidirectional"))
    )
    (net (code "70") (name "unconnected-(U$3-PD5(XCK{slash}CTS)-Pad22)") (class "Default")
      (node (ref "U$3") (pin "22") (pinfunction "PD5(XCK/CTS)_22") (pintype "bidirectional"))
    )
    (net (code "71") (name "unconnected-(U$3-PE6(INT.6{slash}AIN0)-Pad1)") (class "Default")
      (node (ref "U$3") (pin "1") (pinfunction "PE6(INT.6/AIN0)_1") (pintype "bidirectional"))
    )
    (net (code "72") (name "unconnected-(X2-Pad4)") (class "Default")
      (node (ref "X2") (pin "4") (pinfunction "4_4") (pintype "passive"))
    )
  )
)
